# Watchdog_Reset.net
KiCad netlist of a schematic drawn in Altium Designer
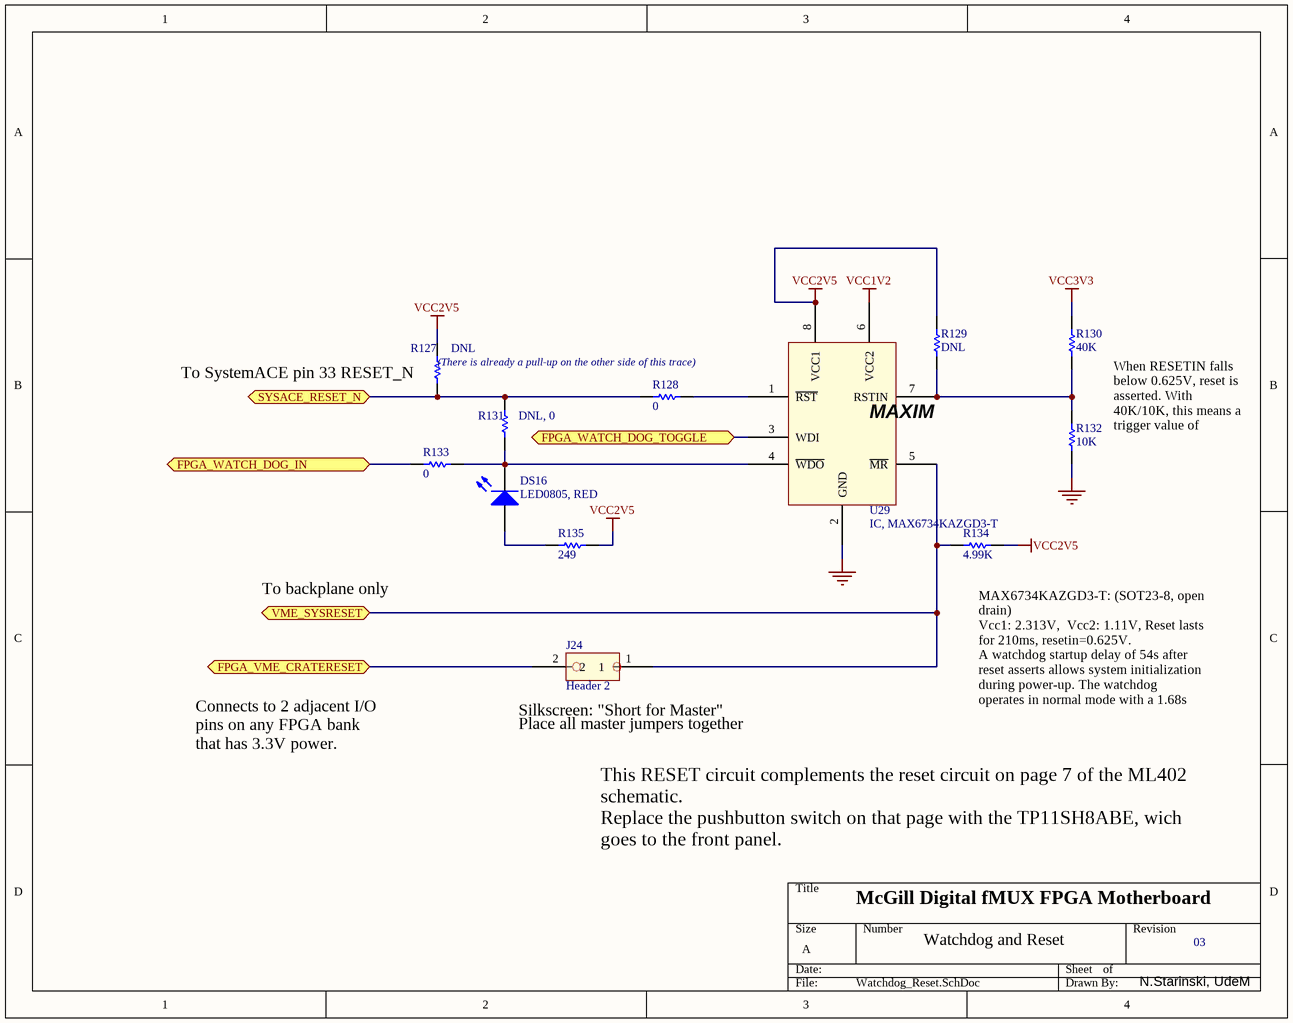
[diagram p0: Watchdog_Reset.SchDoc]

(export (version "E")
  (design (tool "Eeschema 10.0.6"))
  (components
    (comp (ref "DS16")
      (value "LED0805, RED")
      (footprint "SMD _LED")
      (description "LED 0805 LTST-C170CKT")
      (fields (field (name "PUBLISHER") "Altium Limited"))
      (libsource (lib "Miscellaneous Devices 02") (part "LED3"))
    )
    (comp (ref "J24")
      (value "Header 2")
      (footprint "HDR1X2")
      (description "Header, 0.1\" 2-Pin straight")
      (libsource (lib "MyComp1") (part "Jumper_100mil"))
    )
    (comp (ref "R127")
      (value "DNL")
      (footprint "CR1608-0603")
      (description "Semiconductor Resistor")
      (fields (field (name "PUBLISHER") "Altium Limited"))
      (libsource (lib "Miscellaneous Devices") (part "Res Semi"))
    )
    (comp (ref "R128")
      (value "0")
      (footprint "CR1608-0603")
      (description "Resistor 0603")
      (fields (field (name "PUBLISHER") "Altium Limited"))
      (libsource (lib "Miscellaneous Devices") (part "Res Semi"))
    )
    (comp (ref "R129")
      (value "DNL")
      (footprint "CR1608-0603")
      (description "Semiconductor Resistor")
      (fields (field (name "PUBLISHER") "Altium Limited"))
      (libsource (lib "Miscellaneous Devices") (part "Res Semi"))
    )
    (comp (ref "R130")
      (value "40K")
      (footprint "CR1608-0603")
      (description "Resistor 0603")
      (fields (field (name "PUBLISHER") "Altium Limited"))
      (libsource (lib "Miscellaneous Devices") (part "Res Semi"))
    )
    (comp (ref "R131")
      (value "DNL, 0")
      (footprint "CR1608-0603")
      (description "Resistor 0603")
      (fields (field (name "PUBLISHER") "Altium Limited"))
      (libsource (lib "Miscellaneous Devices") (part "Res Semi"))
    )
    (comp (ref "R132")
      (value "10K")
      (footprint "CR1608-0603")
      (description "Resistor 0603")
      (fields (field (name "PUBLISHER") "Altium Limited"))
      (libsource (lib "Miscellaneous Devices") (part "Res Semi"))
    )
    (comp (ref "R133")
      (value "0")
      (footprint "CR1608-0603")
      (description "Resistor 0603")
      (fields (field (name "PUBLISHER") "Altium Limited"))
      (libsource (lib "Miscellaneous Devices") (part "Res Semi"))
    )
    (comp (ref "R134")
      (value "4.99K")
      (footprint "CR1608-0603")
      (description "Resistor 0603")
      (fields (field (name "PUBLISHER") "Altium Limited"))
      (libsource (lib "Miscellaneous Devices") (part "Res Semi"))
    )
    (comp (ref "R135")
      (value "249")
      (footprint "CR1608-0603")
      (description "Resistor 0603")
      (fields (field (name "PUBLISHER") "Altium Limited"))
      (libsource (lib "Miscellaneous Devices") (part "Res Semi"))
    )
    (comp (ref "U29")
      (value "IC, MAX6734KAZGD3-T")
      (footprint "SOP23-8")
      (description "uP Supervisory Circuit")
      (libsource (lib "Maxim Power Mgt Supervisory Circuit") (part "MAX6734"))
    )
  )
  (nets
    (net (code "1") (name "/FPGA_VME_CRATERESET") (class "Default")
      (node (ref "J24") (pin "2") (pinfunction "2_2") (pintype "passive"))
    )
    (net (code "2") (name "/FPGA_WATCH_DOG_IN") (class "Default")
      (node (ref "R133") (pin "1") (pinfunction "1_1") (pintype "passive"))
    )
    (net (code "3") (name "/FPGA_WATCH_DOG_TOGGLE") (class "Default")
      (node (ref "U29") (pin "3") (pinfunction "WDI_3") (pintype "passive"))
    )
    (net (code "4") (name "/SYSACE_RESET_N") (class "Default")
      (node (ref "R127") (pin "1") (pinfunction "1_1") (pintype "passive"))
      (node (ref "R128") (pin "1") (pinfunction "1_1") (pintype "passive"))
      (node (ref "R131") (pin "2") (pinfunction "2_2") (pintype "passive"))
    )
    (net (code "5") (name "/VME_SYSRESET") (class "Default")
      (node (ref "J24") (pin "1") (pinfunction "1_1") (pintype "passive"))
      (node (ref "R134") (pin "1") (pinfunction "1_1") (pintype "passive"))
      (node (ref "U29") (pin "5") (pinfunction "~{MR}_5") (pintype "passive"))
    )
    (net (code "6") (name "GND") (class "Default")
      (node (ref "R132") (pin "1") (pinfunction "1_1") (pintype "passive"))
      (node (ref "U29") (pin "2") (pinfunction "GND_2") (pintype "power_in"))
    )
    (net (code "7") (name "Net-(DS16-A)") (class "Default")
      (node (ref "DS16") (pin "1") (pinfunction "A_1") (pintype "passive"))
      (node (ref "R135") (pin "1") (pinfunction "1_1") (pintype "passive"))
    )
    (net (code "8") (name "Net-(DS16-K)") (class "Default")
      (node (ref "DS16") (pin "2") (pinfunction "K_2") (pintype "passive"))
      (node (ref "R131") (pin "1") (pinfunction "1_1") (pintype "passive"))
      (node (ref "R133") (pin "2") (pinfunction "2_2") (pintype "passive"))
      (node (ref "U29") (pin "4") (pinfunction "~{WDO}_4") (pintype "passive"))
    )
    (net (code "9") (name "Net-(U29-RSTIN)") (class "Default")
      (node (ref "R129") (pin "1") (pinfunction "1_1") (pintype "passive"))
      (node (ref "R130") (pin "1") (pinfunction "1_1") (pintype "passive"))
      (node (ref "R132") (pin "2") (pinfunction "2_2") (pintype "passive"))
      (node (ref "U29") (pin "7") (pinfunction "RSTIN_7") (pintype "passive"))
    )
    (net (code "10") (name "Net-(U29-~{RST})") (class "Default")
      (node (ref "R128") (pin "2") (pinfunction "2_2") (pintype "passive"))
      (node (ref "U29") (pin "1") (pinfunction "~{RST}_1") (pintype "passive"))
    )
    (net (code "11") (name "VCC1V2") (class "Default")
      (node (ref "U29") (pin "6") (pinfunction "VCC2_6") (pintype "power_in"))
    )
    (net (code "12") (name "VCC2V5") (class "Default")
      (node (ref "R127") (pin "2") (pinfunction "2_2") (pintype "passive"))
      (node (ref "R129") (pin "2") (pinfunction "2_2") (pintype "passive"))
      (node (ref "R134") (pin "2") (pinfunction "2_2") (pintype "passive"))
      (node (ref "R135") (pin "2") (pinfunction "2_2") (pintype "passive"))
      (node (ref "U29") (pin "8") (pinfunction "VCC1_8") (pintype "power_in"))
    )
    (net (code "13") (name "VCC3V3") (class "Default")
      (node (ref "R130") (pin "2") (pinfunction "2_2") (pintype "passive"))
    )
  )
)
